# power-v1v8.net
KiCad netlist of a schematic drawn in Altium Designer
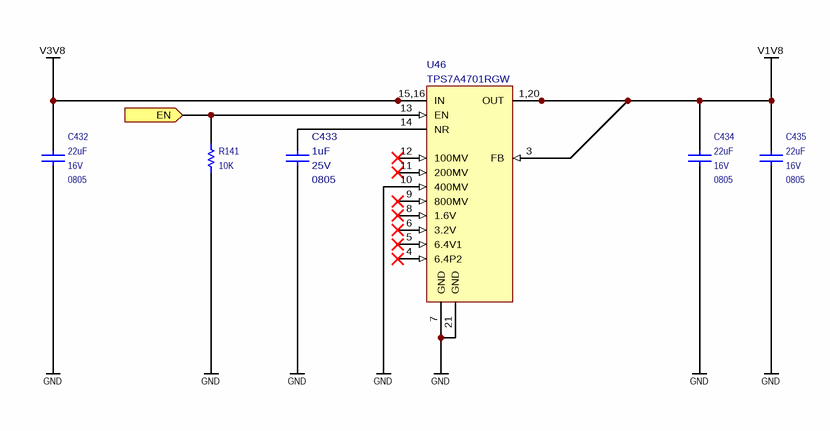
[diagram p0: power-v1v8.SchDoc]

(export (version "E")
  (design (tool "Eeschema 10.0.6"))
  (components
    (comp (ref "C432")
      (value "22uF")
      (footprint "generic:CAPC200X125X145L45N")
      (description "Ceramic Capacitor 22uF ±10% 16V X5R 0805")
      (fields
        (field (name "MANUFACTURER") "Samsung")
        (field (name "VOLTAGE") "16V")
        (field (name "PACKAGE") "0805")
        (field (name "TOLERANCE") "±10%")
      )
      (libsource (lib "generic") (part "CAP 0603"))
    )
    (comp (ref "C433")
      (value "1uF")
      (footprint "CAPC200X125X145L45N")
      (description "Ceramic Capacitor 1uF ±10% 25V X7R 0805")
      (fields
        (field (name "MANUFACTURER") "Taiyo Yuden")
        (field (name "TOLERANCE") "±10%")
        (field (name "PACKAGE") "0805")
        (field (name "VOLTAGE") "25V")
      )
      (libsource (lib "capacitors") (part "CAP"))
    )
    (comp (ref "C434")
      (value "22uF")
      (footprint "generic:CAPC200X125X145L45N")
      (description "Ceramic Capacitor 22uF ±10% 16V X5R 0805")
      (fields
        (field (name "MANUFACTURER") "Samsung")
        (field (name "VOLTAGE") "16V")
        (field (name "PACKAGE") "0805")
        (field (name "TOLERANCE") "±10%")
      )
      (libsource (lib "generic") (part "CAP 0603"))
    )
    (comp (ref "C435")
      (value "22uF")
      (footprint "generic:CAPC200X125X145L45N")
      (description "Ceramic Capacitor 22uF ±10% 16V X5R 0805")
      (fields
        (field (name "MANUFACTURER") "Samsung")
        (field (name "VOLTAGE") "16V")
        (field (name "PACKAGE") "0805")
        (field (name "TOLERANCE") "±10%")
      )
      (libsource (lib "generic") (part "CAP 0603"))
    )
    (comp (ref "R141")
      (value "10K")
      (footprint "generic:RESC1005X40N")
      (description "Thick Film Resistor 10k ±1% 0.1W 50V 0402")
      (fields (field (name "MANUFACTURER") "Panasonic") (field (name "TOLERANCE") "±1%"))
      (libsource (lib "Graviton") (part "RES 0402"))
    )
    (comp (ref "U46")
      (value "TPS7A4701RGW")
      (footprint "QFN65P500X500X100-21N")
      (description "Low-Dropout Linear Regulator 20-VQFN")
      (fields (field (name "MANUFACTURER") "Texas Instruments"))
      (libsource (lib "ti") (part "TPS7A4701RGW_1"))
    )
  )
  (nets
    (net (code "1") (name "/EN") (class "Default")
      (node (ref "R141") (pin "1") (pinfunction "1_1") (pintype "passive"))
      (node (ref "U46") (pin "13") (pinfunction "EN_13") (pintype "input"))
    )
    (net (code "2") (name "GND") (class "Default")
      (node (ref "C432") (pin "1") (pinfunction "1_1") (pintype "passive"))
      (node (ref "C433") (pin "2") (pinfunction "2_2") (pintype "passive"))
      (node (ref "C434") (pin "1") (pinfunction "1_1") (pintype "passive"))
      (node (ref "C435") (pin "1") (pinfunction "1_1") (pintype "passive"))
      (node (ref "R141") (pin "2") (pinfunction "2_2") (pintype "passive"))
      (node (ref "U46") (pin "10") (pinfunction "400MV_10") (pintype "input"))
      (node (ref "U46") (pin "21") (pinfunction "GND_21") (pintype "power_in"))
      (node (ref "U46") (pin "7") (pinfunction "GND_7") (pintype "power_in"))
    )
    (net (code "3") (name "Net-(U46-NR)") (class "Default")
      (node (ref "C433") (pin "1") (pinfunction "1_1") (pintype "passive"))
      (node (ref "U46") (pin "14") (pinfunction "NR_14") (pintype "passive"))
    )
    (net (code "4") (name "V1V8") (class "Default")
      (node (ref "C434") (pin "2") (pinfunction "2_2") (pintype "passive"))
      (node (ref "C435") (pin "2") (pinfunction "2_2") (pintype "passive"))
      (node (ref "U46") (pin "1") (pinfunction "OUT_1") (pintype "passive"))
      (node (ref "U46") (pin "20") (pinfunction "OUT_20") (pintype "passive"))
      (node (ref "U46") (pin "3") (pinfunction "FB_3") (pintype "input"))
    )
    (net (code "5") (name "V3V8") (class "Default")
      (node (ref "C432") (pin "2") (pinfunction "2_2") (pintype "passive"))
      (node (ref "U46") (pin "15") (pinfunction "IN_15") (pintype "passive"))
      (node (ref "U46") (pin "16") (pinfunction "IN_16") (pintype "passive"))
    )
    (net (code "6") (name "unconnected-(U46-1.6V-Pad8)") (class "Default")
      (node (ref "U46") (pin "8") (pinfunction "1.6V_8") (pintype "input+no_connect"))
    )
    (net (code "7") (name "unconnected-(U46-3.2V-Pad6)") (class "Default")
      (node (ref "U46") (pin "6") (pinfunction "3.2V_6") (pintype "input+no_connect"))
    )
    (net (code "8") (name "unconnected-(U46-6.4P2-Pad4)") (class "Default")
      (node (ref "U46") (pin "4") (pinfunction "6.4P2_4") (pintype "input+no_connect"))
    )
    (net (code "9") (name "unconnected-(U46-6.4V1-Pad5)") (class "Default")
      (node (ref "U46") (pin "5") (pinfunction "6.4V1_5") (pintype "input+no_connect"))
    )
    (net (code "10") (name "unconnected-(U46-100MV-Pad12)") (class "Default")
      (node (ref "U46") (pin "12") (pinfunction "100MV_12") (pintype "input+no_connect"))
    )
    (net (code "11") (name "unconnected-(U46-200MV-Pad11)") (class "Default")
      (node (ref "U46") (pin "11") (pinfunction "200MV_11") (pintype "input+no_connect"))
    )
    (net (code "12") (name "unconnected-(U46-800MV-Pad9)") (class "Default")
      (node (ref "U46") (pin "9") (pinfunction "800MV_9") (pintype "input+no_connect"))
    )
  )
)
